# Double_Gen.net
KiCad netlist of a schematic drawn in EAGLE
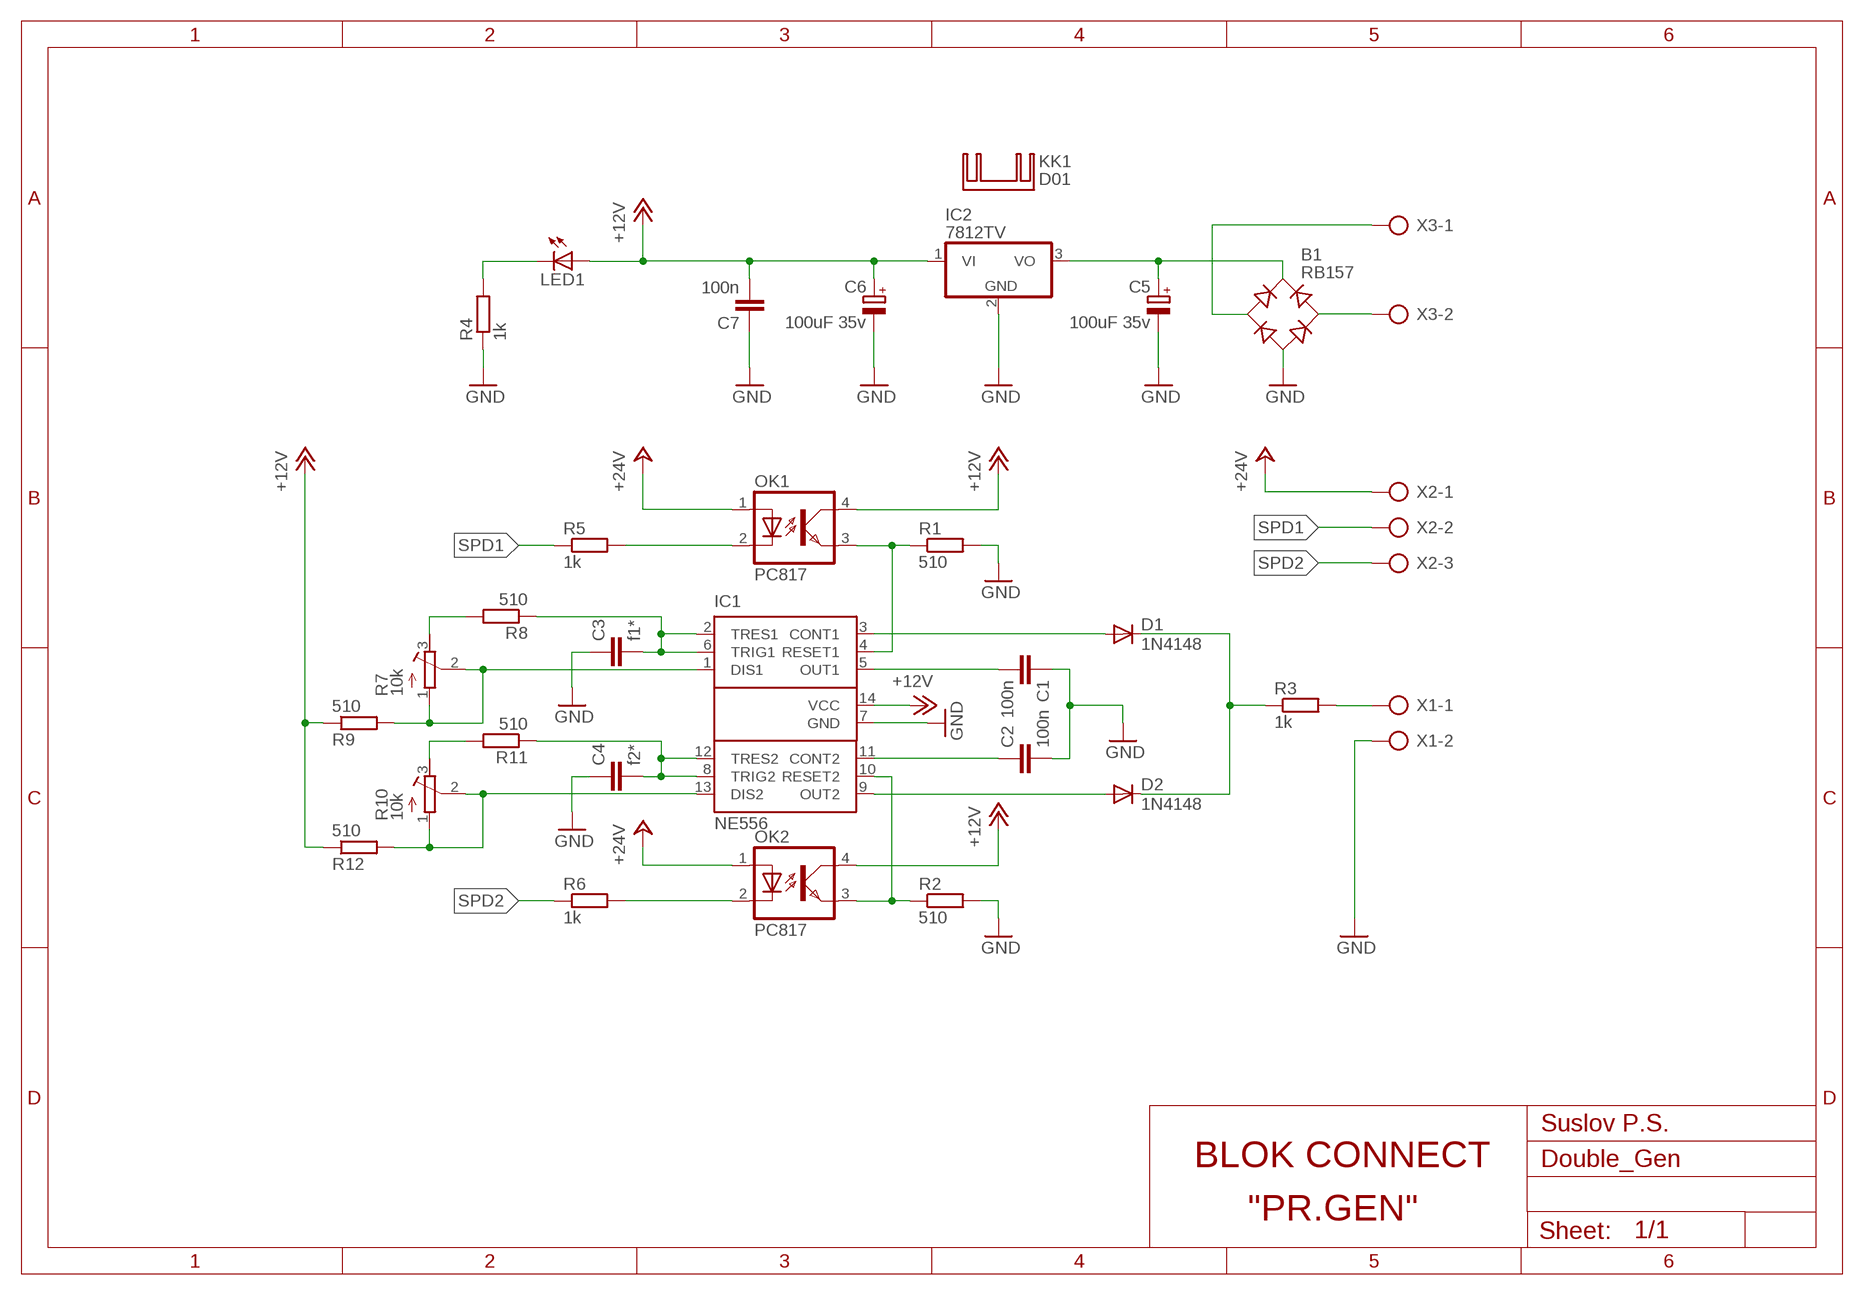
[diagram p0: schematic, sheet 1]

(export (version "E")
  (design (tool "Eeschema 10.0.6"))
  (components
    (comp (ref "B1")
      (value "RB157")
      (footprint "eagle-import:RB1A")
      (libsource (lib "eagle-import") (part "RB1A"))
    )
    (comp (ref "C1")
      (value "100n")
      (footprint "eagle-import:C050-050X075")
      (libsource (lib "eagle-import") (part "C-EU050-050X075"))
    )
    (comp (ref "C2")
      (value "100n")
      (footprint "eagle-import:C050-050X075")
      (libsource (lib "eagle-import") (part "C-EU050-050X075"))
    )
    (comp (ref "C3")
      (value "f1*")
      (footprint "eagle-import:C050-050X075")
      (libsource (lib "eagle-import") (part "C-EU050-050X075"))
    )
    (comp (ref "C4")
      (value "f2*")
      (footprint "eagle-import:C050-050X075")
      (libsource (lib "eagle-import") (part "C-EU050-050X075"))
    )
    (comp (ref "C5")
      (value "100uF 35v")
      (footprint "eagle-import:E3,5-8")
      (libsource (lib "eagle-import") (part "CPOL-EUE3.5-8"))
    )
    (comp (ref "C6")
      (value "100uF 35v")
      (footprint "eagle-import:E3,5-8")
      (libsource (lib "eagle-import") (part "CPOL-EUE3.5-8"))
    )
    (comp (ref "C7")
      (value "100n")
      (footprint "eagle-import:C050-050X075")
      (libsource (lib "eagle-import") (part "C-EU050-050X075"))
    )
    (comp (ref "D1")
      (value "1N4148")
      (footprint "eagle-import:DO35-7")
      (libsource (lib "eagle-import") (part "1N4148DO35-7"))
    )
    (comp (ref "D2")
      (value "1N4148")
      (footprint "eagle-import:DO35-7")
      (libsource (lib "eagle-import") (part "1N4148DO35-7"))
    )
    (comp (ref "IC1")
      (value "NE556")
      (footprint "eagle-import:DIL14")
      (libsource (lib "eagle-import") (part "NE556"))
    )
    (comp (ref "IC2")
      (value "7812TV")
      (footprint "eagle-import:TO220V")
      (libsource (lib "eagle-import") (part "78TV12"))
    )
    (comp (ref "KK1")
      (value "D01")
      (footprint "eagle-import:D02S")
      (libsource (lib "eagle-import") (part "D02S"))
    )
    (comp (ref "LED1")
      (value "LED5MM")
      (footprint "eagle-import:LED5MM")
      (libsource (lib "eagle-import") (part "LED5MM"))
    )
    (comp (ref "OK1")
      (value "PC817")
      (footprint "eagle-import:DIL04")
      (fields (field (name "MPN") "PC817X4J000F"))
      (libsource (lib "eagle-import") (part "PC817"))
    )
    (comp (ref "OK2")
      (value "PC817")
      (footprint "eagle-import:DIL04")
      (fields (field (name "MPN") "PC817X4J000F"))
      (libsource (lib "eagle-import") (part "PC817"))
    )
    (comp (ref "R1")
      (value "510")
      (footprint "eagle-import:0207_10")
      (libsource (lib "eagle-import") (part "R-EU_0207/10"))
    )
    (comp (ref "R2")
      (value "510")
      (footprint "eagle-import:0207_10")
      (libsource (lib "eagle-import") (part "R-EU_0207/10"))
    )
    (comp (ref "R3")
      (value "1k")
      (footprint "eagle-import:0207_10")
      (libsource (lib "eagle-import") (part "R-EU_0207/10"))
    )
    (comp (ref "R4")
      (value "1k")
      (footprint "eagle-import:0207_10")
      (libsource (lib "eagle-import") (part "R-EU_0207/10"))
    )
    (comp (ref "R5")
      (value "1k")
      (footprint "eagle-import:0207_10")
      (libsource (lib "eagle-import") (part "R-EU_0207/10"))
    )
    (comp (ref "R6")
      (value "1k")
      (footprint "eagle-import:0207_10")
      (libsource (lib "eagle-import") (part "R-EU_0207/10"))
    )
    (comp (ref "R7")
      (value "10k")
      (footprint "eagle-import:RTRIM64W")
      (libsource (lib "eagle-import") (part "R-TRIMM64W"))
    )
    (comp (ref "R8")
      (value "510")
      (footprint "eagle-import:0207_10")
      (libsource (lib "eagle-import") (part "R-EU_0207/10"))
    )
    (comp (ref "R9")
      (value "510")
      (footprint "eagle-import:0207_10")
      (libsource (lib "eagle-import") (part "R-EU_0207/10"))
    )
    (comp (ref "R10")
      (value "10k")
      (footprint "eagle-import:RTRIM64W")
      (libsource (lib "eagle-import") (part "R-TRIMM64W"))
    )
    (comp (ref "R11")
      (value "510")
      (footprint "eagle-import:0207_10")
      (libsource (lib "eagle-import") (part "R-EU_0207/10"))
    )
    (comp (ref "R12")
      (value "510")
      (footprint "eagle-import:0207_10")
      (libsource (lib "eagle-import") (part "R-EU_0207/10"))
    )
    (comp (ref "X1")
      (value "AK500/2")
      (footprint "eagle-import:AK500_2")
      (libsource (lib "eagle-import") (part "AK500/2"))
    )
    (comp (ref "X2")
      (value "AK500/3")
      (footprint "eagle-import:AK500_3")
      (libsource (lib "eagle-import") (part "AK500/3"))
    )
    (comp (ref "X3")
      (value "AK500/2")
      (footprint "eagle-import:AK500_2")
      (libsource (lib "eagle-import") (part "AK500/2"))
    )
  )
  (nets
    (net (code "1") (name "+12V") (class "Default")
      (node (ref "C6") (pin "+") (pinfunction "+_+") (pintype "passive"))
      (node (ref "C7") (pin "1") (pinfunction "1_1") (pintype "passive"))
      (node (ref "IC1") (pin "14") (pinfunction "VCC_14") (pintype "power_in"))
      (node (ref "IC2") (pin "1") (pinfunction "VI_1") (pintype "input"))
      (node (ref "LED1") (pin "A") (pinfunction "A_A") (pintype "passive"))
      (node (ref "OK1") (pin "4") (pinfunction "COL_4") (pintype "passive"))
      (node (ref "OK2") (pin "4") (pinfunction "COL_4") (pintype "passive"))
      (node (ref "R12") (pin "1") (pinfunction "1_1") (pintype "passive"))
      (node (ref "R9") (pin "1") (pinfunction "1_1") (pintype "passive"))
    )
    (net (code "2") (name "+24V") (class "Default")
      (node (ref "OK1") (pin "1") (pinfunction "A_1") (pintype "passive"))
      (node (ref "OK2") (pin "1") (pinfunction "A_1") (pintype "passive"))
      (node (ref "X2") (pin "1") (pinfunction "KL_1") (pintype "passive"))
    )
    (net (code "3") (name "GND") (class "Default")
      (node (ref "B1") (pin "-") (pinfunction "-_-") (pintype "passive"))
      (node (ref "C1") (pin "2") (pinfunction "2_2") (pintype "passive"))
      (node (ref "C2") (pin "2") (pinfunction "2_2") (pintype "passive"))
      (node (ref "C3") (pin "2") (pinfunction "2_2") (pintype "passive"))
      (node (ref "C4") (pin "2") (pinfunction "2_2") (pintype "passive"))
      (node (ref "C5") (pin "-") (pinfunction "-_-") (pintype "passive"))
      (node (ref "C6") (pin "-") (pinfunction "-_-") (pintype "passive"))
      (node (ref "C7") (pin "2") (pinfunction "2_2") (pintype "passive"))
      (node (ref "IC1") (pin "7") (pinfunction "GND_7") (pintype "power_in"))
      (node (ref "IC2") (pin "2") (pinfunction "GND_2") (pintype "passive"))
      (node (ref "R1") (pin "2") (pinfunction "2_2") (pintype "passive"))
      (node (ref "R2") (pin "2") (pinfunction "2_2") (pintype "passive"))
      (node (ref "R4") (pin "1") (pinfunction "1_1") (pintype "passive"))
      (node (ref "X1") (pin "2") (pinfunction "KL_2") (pintype "passive"))
    )
    (net (code "4") (name "Net-(D1-PadC)") (class "Default")
      (node (ref "D1") (pin "C") (pinfunction "C_C") (pintype "passive"))
      (node (ref "D2") (pin "C") (pinfunction "C_C") (pintype "passive"))
      (node (ref "R3") (pin "1") (pinfunction "1_1") (pintype "passive"))
    )
    (net (code "5") (name "Net-(IC1-CONT1)") (class "Default")
      (node (ref "D1") (pin "A") (pinfunction "A_A") (pintype "passive"))
      (node (ref "IC1") (pin "3") (pinfunction "CONT1_3") (pintype "input"))
    )
    (net (code "6") (name "Net-(IC1-CONT2)") (class "Default")
      (node (ref "C2") (pin "1") (pinfunction "1_1") (pintype "passive"))
      (node (ref "IC1") (pin "11") (pinfunction "CONT2_11") (pintype "input"))
    )
    (net (code "7") (name "Net-(IC1-DIS1)") (class "Default")
      (node (ref "IC1") (pin "1") (pinfunction "DIS1_1") (pintype "input"))
      (node (ref "R7") (pin "1") (pinfunction "A_1") (pintype "passive"))
      (node (ref "R7") (pin "2") (pinfunction "S_2") (pintype "passive"))
      (node (ref "R9") (pin "2") (pinfunction "2_2") (pintype "passive"))
    )
    (net (code "8") (name "Net-(IC1-DIS2)") (class "Default")
      (node (ref "IC1") (pin "13") (pinfunction "DIS2_13") (pintype "input"))
      (node (ref "R10") (pin "1") (pinfunction "A_1") (pintype "passive"))
      (node (ref "R10") (pin "2") (pinfunction "S_2") (pintype "passive"))
      (node (ref "R12") (pin "2") (pinfunction "2_2") (pintype "passive"))
    )
    (net (code "9") (name "Net-(IC1-OUT1)") (class "Default")
      (node (ref "C1") (pin "1") (pinfunction "1_1") (pintype "passive"))
      (node (ref "IC1") (pin "5") (pinfunction "OUT1_5") (pintype "output"))
    )
    (net (code "10") (name "Net-(IC1-OUT2)") (class "Default")
      (node (ref "D2") (pin "A") (pinfunction "A_A") (pintype "passive"))
      (node (ref "IC1") (pin "9") (pinfunction "OUT2_9") (pintype "output"))
    )
    (net (code "11") (name "Net-(IC1-RESET1)") (class "Default")
      (node (ref "IC1") (pin "4") (pinfunction "RESET1_4") (pintype "input"))
      (node (ref "OK1") (pin "3") (pinfunction "EMIT_3") (pintype "passive"))
      (node (ref "R1") (pin "1") (pinfunction "1_1") (pintype "passive"))
    )
    (net (code "12") (name "Net-(IC1-RESET2)") (class "Default")
      (node (ref "IC1") (pin "10") (pinfunction "RESET2_10") (pintype "input"))
      (node (ref "OK2") (pin "3") (pinfunction "EMIT_3") (pintype "passive"))
      (node (ref "R2") (pin "1") (pinfunction "1_1") (pintype "passive"))
    )
    (net (code "13") (name "Net-(IC1-TRES1)") (class "Default")
      (node (ref "C3") (pin "1") (pinfunction "1_1") (pintype "passive"))
      (node (ref "IC1") (pin "2") (pinfunction "TRES1_2") (pintype "input"))
      (node (ref "IC1") (pin "6") (pinfunction "TRIG1_6") (pintype "input"))
      (node (ref "R8") (pin "1") (pinfunction "1_1") (pintype "passive"))
    )
    (net (code "14") (name "Net-(IC1-TRES2)") (class "Default")
      (node (ref "C4") (pin "1") (pinfunction "1_1") (pintype "passive"))
      (node (ref "IC1") (pin "12") (pinfunction "TRES2_12") (pintype "input"))
      (node (ref "IC1") (pin "8") (pinfunction "TRIG2_8") (pintype "input"))
      (node (ref "R11") (pin "1") (pinfunction "1_1") (pintype "passive"))
    )
    (net (code "15") (name "Net-(IC2-VO)") (class "Default")
      (node (ref "B1") (pin "+") (pinfunction "+_+") (pintype "passive"))
      (node (ref "C5") (pin "+") (pinfunction "+_+") (pintype "passive"))
      (node (ref "IC2") (pin "3") (pinfunction "VO_3") (pintype "passive"))
    )
    (net (code "16") (name "Net-(LED1-C)") (class "Default")
      (node (ref "LED1") (pin "K") (pinfunction "C_K") (pintype "passive"))
      (node (ref "R4") (pin "2") (pinfunction "2_2") (pintype "passive"))
    )
    (net (code "17") (name "Net-(OK1-C)") (class "Default")
      (node (ref "OK1") (pin "2") (pinfunction "C_2") (pintype "passive"))
      (node (ref "R5") (pin "2") (pinfunction "2_2") (pintype "passive"))
    )
    (net (code "18") (name "Net-(OK2-C)") (class "Default")
      (node (ref "OK2") (pin "2") (pinfunction "C_2") (pintype "passive"))
      (node (ref "R6") (pin "2") (pinfunction "2_2") (pintype "passive"))
    )
    (net (code "19") (name "Net-(R7-E)") (class "Default")
      (node (ref "R7") (pin "3") (pinfunction "E_3") (pintype "passive"))
      (node (ref "R8") (pin "2") (pinfunction "2_2") (pintype "passive"))
    )
    (net (code "20") (name "Net-(R10-E)") (class "Default")
      (node (ref "R10") (pin "3") (pinfunction "E_3") (pintype "passive"))
      (node (ref "R11") (pin "2") (pinfunction "2_2") (pintype "passive"))
    )
    (net (code "21") (name "Net-(X1A-KL)") (class "Default")
      (node (ref "R3") (pin "2") (pinfunction "2_2") (pintype "passive"))
      (node (ref "X1") (pin "1") (pinfunction "KL_1") (pintype "passive"))
    )
    (net (code "22") (name "Net-(X3A-KL)") (class "Default")
      (node (ref "B1") (pin "AC1") (pinfunction "AC1_AC1") (pintype "passive"))
      (node (ref "X3") (pin "1") (pinfunction "KL_1") (pintype "passive"))
    )
    (net (code "23") (name "Net-(X3B-KL)") (class "Default")
      (node (ref "B1") (pin "AC2") (pinfunction "AC2_AC2") (pintype "passive"))
      (node (ref "X3") (pin "2") (pinfunction "KL_2") (pintype "passive"))
    )
    (net (code "24") (name "SPD1") (class "Default")
      (node (ref "R5") (pin "1") (pinfunction "1_1") (pintype "passive"))
      (node (ref "X2") (pin "2") (pinfunction "KL_2") (pintype "passive"))
    )
    (net (code "25") (name "SPD2") (class "Default")
      (node (ref "R6") (pin "1") (pinfunction "1_1") (pintype "passive"))
      (node (ref "X2") (pin "3") (pinfunction "KL_3") (pintype "passive"))
    )
  )
)
